# 02_-_EasyEDA.net
KiCad netlist of a schematic drawn in EasyEDA
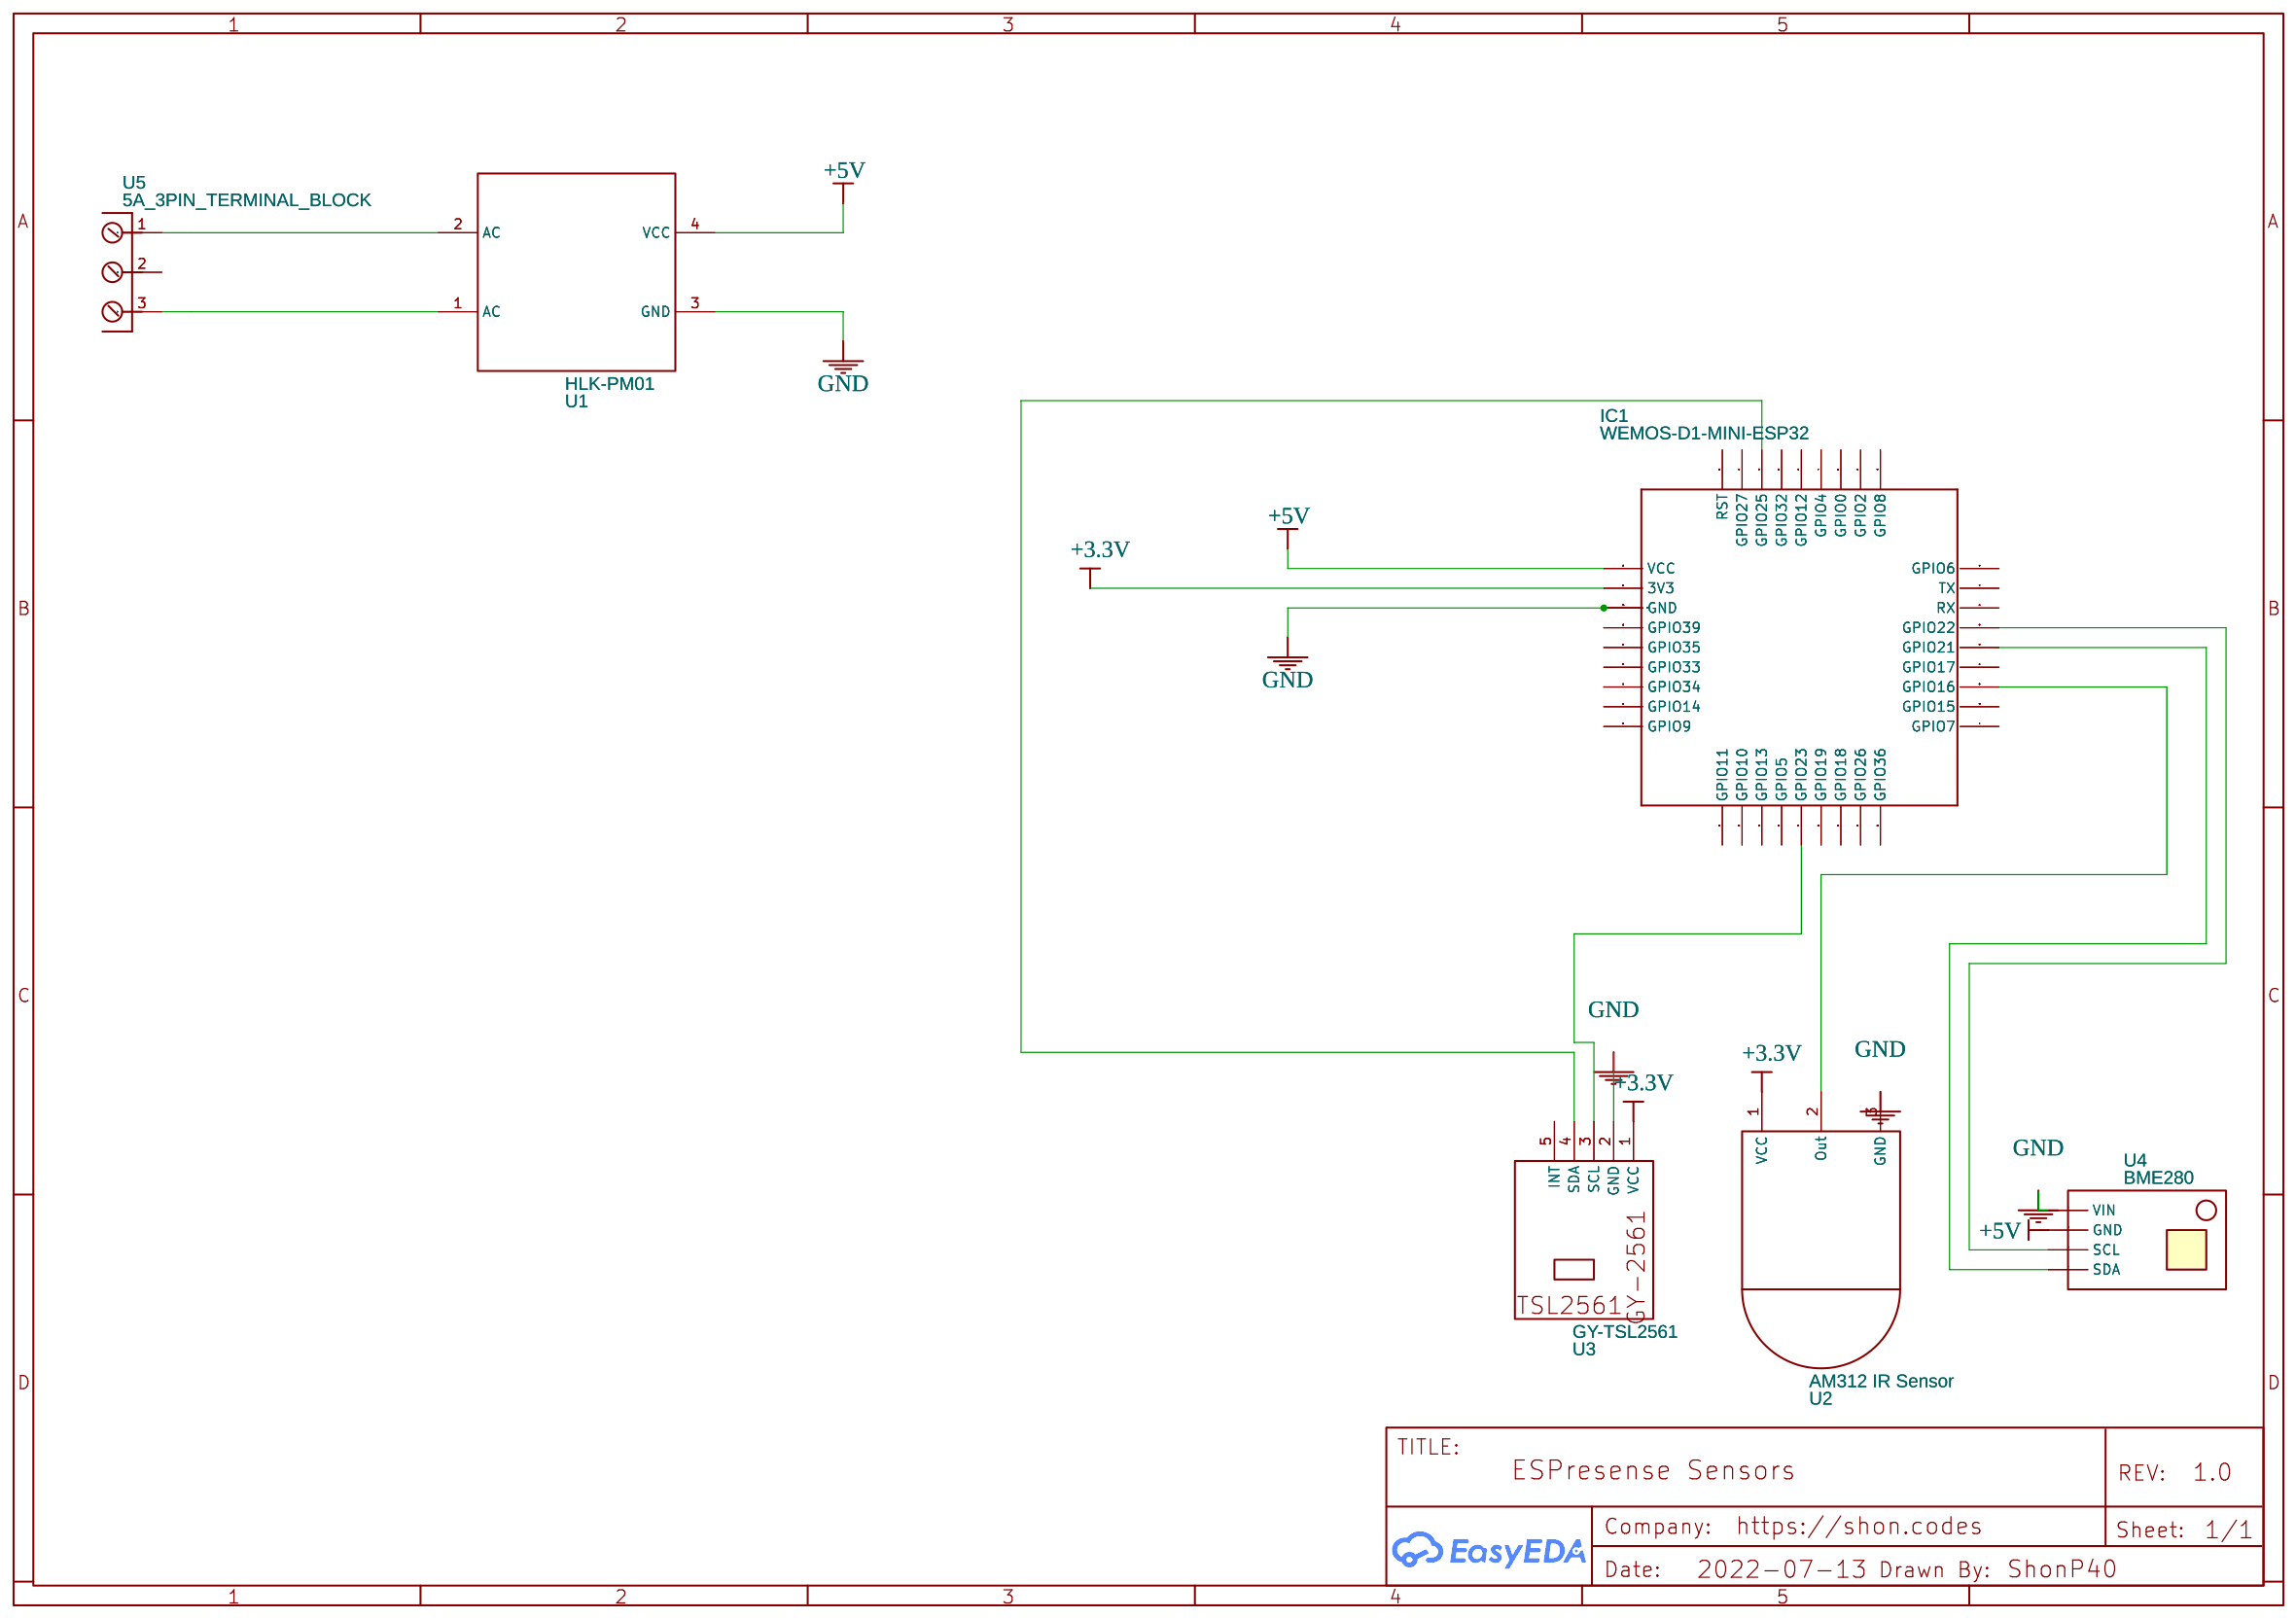
[diagram p0: schematic sheet]

(export (version "E")
  (design (tool "Eeschema 10.0.6"))
  (components
    (comp (ref "IC1") (value "WEMOS-D1-MINI-ESP32") (libsource (lib "") (part "WEMOS-D1-MINI-ESP32")))
    (comp (ref "U1") (value "HLK-PM01") (libsource (lib "") (part "HLK-PM01")))
    (comp (ref "U2") (value "AM312 IR Sensor") (libsource (lib "") (part "AM312 IR Sensor")))
    (comp (ref "U3") (value "GY-TSL2561") (libsource (lib "") (part "GY-TSL2561")))
    (comp (ref "U4") (value "BME280") (libsource (lib "") (part "BME280")))
    (comp (ref "U5") (value "5A_3PIN_TERMINAL_BLOCK") (libsource (lib "") (part "5A_3PIN_TERMINAL_BLOCK")))
  )
  (nets
    (net (code "1") (name "+3.3V") (class "Default")
      (node (ref "IC1") (pin "3V3") (pinfunction "3V3_3V3") (pintype "bidirectional"))
      (node (ref "U2") (pin "1") (pinfunction "VCC_1") (pintype "unspecified"))
      (node (ref "U3") (pin "1") (pinfunction "VCC_1") (pintype "unspecified"))
    )
    (net (code "2") (name "+5V") (class "Default")
      (node (ref "IC1") (pin "VCC") (pinfunction "VCC_VCC") (pintype "bidirectional"))
      (node (ref "U1") (pin "4") (pinfunction "VCC_4") (pintype "unspecified"))
      (node (ref "U4") (pin "2") (pinfunction "GND_2") (pintype "unspecified"))
    )
    (net (code "3") (name "GND") (class "Default")
      (node (ref "IC1") (pin "GND1") (pinfunction "GND_GND1") (pintype "bidirectional"))
      (node (ref "IC1") (pin "GND2") (pinfunction "GND_GND2") (pintype "bidirectional"))
      (node (ref "IC1") (pin "GND3") (pinfunction "GND_GND3") (pintype "bidirectional"))
      (node (ref "U1") (pin "3") (pinfunction "GND_3") (pintype "unspecified"))
      (node (ref "U2") (pin "3") (pinfunction "GND_3") (pintype "unspecified"))
      (node (ref "U3") (pin "2") (pinfunction "GND_2") (pintype "unspecified"))
      (node (ref "U4") (pin "1") (pinfunction "VIN_1") (pintype "unspecified"))
    )
    (net (code "4") (name "Net-(IC1-GPIO16)") (class "Default")
      (node (ref "IC1") (pin "16") (pinfunction "GPIO16_16") (pintype "bidirectional"))
      (node (ref "U2") (pin "2") (pinfunction "Out_2") (pintype "unspecified"))
    )
    (net (code "5") (name "Net-(IC1-GPIO21)") (class "Default")
      (node (ref "IC1") (pin "21") (pinfunction "GPIO21_21") (pintype "bidirectional"))
      (node (ref "U4") (pin "4") (pinfunction "SDA_4") (pintype "unspecified"))
    )
    (net (code "6") (name "Net-(IC1-GPIO22)") (class "Default")
      (node (ref "IC1") (pin "22") (pinfunction "GPIO22_22") (pintype "bidirectional"))
      (node (ref "U4") (pin "3") (pinfunction "SCL_3") (pintype "unspecified"))
    )
    (net (code "7") (name "Net-(IC1-GPIO23)") (class "Default")
      (node (ref "IC1") (pin "23") (pinfunction "GPIO23_23") (pintype "bidirectional"))
      (node (ref "U3") (pin "3") (pinfunction "SCL_3") (pintype "unspecified"))
    )
    (net (code "8") (name "Net-(IC1-GPIO25)") (class "Default")
      (node (ref "IC1") (pin "25") (pinfunction "GPIO25_25") (pintype "bidirectional"))
      (node (ref "U3") (pin "4") (pinfunction "SDA_4") (pintype "unspecified"))
    )
    (net (code "9") (name "Net-(U1-AC-Pad1)") (class "Default")
      (node (ref "U1") (pin "1") (pinfunction "AC_1") (pintype "unspecified"))
      (node (ref "U5") (pin "3") (pinfunction "3_3") (pintype "unspecified"))
    )
    (net (code "10") (name "Net-(U1-AC-Pad2)") (class "Default")
      (node (ref "U1") (pin "2") (pinfunction "AC_2") (pintype "unspecified"))
      (node (ref "U5") (pin "1") (pinfunction "1_1") (pintype "unspecified"))
    )
    (net (code "11") (name "unconnected-(IC1-GPIO0-Pad0)") (class "Default")
      (node (ref "IC1") (pin "0") (pinfunction "GPIO0_0") (pintype "bidirectional"))
    )
    (net (code "12") (name "unconnected-(IC1-GPIO2-Pad2)") (class "Default")
      (node (ref "IC1") (pin "2") (pinfunction "GPIO2_2") (pintype "bidirectional"))
    )
    (net (code "13") (name "unconnected-(IC1-GPIO4-Pad4)") (class "Default")
      (node (ref "IC1") (pin "4") (pinfunction "GPIO4_4") (pintype "bidirectional"))
    )
    (net (code "14") (name "unconnected-(IC1-GPIO5-Pad5)") (class "Default")
      (node (ref "IC1") (pin "5") (pinfunction "GPIO5_5") (pintype "bidirectional"))
    )
    (net (code "15") (name "unconnected-(IC1-GPIO6-Pad6)") (class "Default")
      (node (ref "IC1") (pin "6") (pinfunction "GPIO6_6") (pintype "bidirectional"))
    )
    (net (code "16") (name "unconnected-(IC1-GPIO7-Pad7)") (class "Default")
      (node (ref "IC1") (pin "7") (pinfunction "GPIO7_7") (pintype "bidirectional"))
    )
    (net (code "17") (name "unconnected-(IC1-GPIO8-Pad8)") (class "Default")
      (node (ref "IC1") (pin "8") (pinfunction "GPIO8_8") (pintype "bidirectional"))
    )
    (net (code "18") (name "unconnected-(IC1-GPIO9-Pad9)") (class "Default")
      (node (ref "IC1") (pin "9") (pinfunction "GPIO9_9") (pintype "bidirectional"))
    )
    (net (code "19") (name "unconnected-(IC1-GPIO10-Pad10)") (class "Default")
      (node (ref "IC1") (pin "10") (pinfunction "GPIO10_10") (pintype "bidirectional"))
    )
    (net (code "20") (name "unconnected-(IC1-GPIO11-Pad11)") (class "Default")
      (node (ref "IC1") (pin "11") (pinfunction "GPIO11_11") (pintype "bidirectional"))
    )
    (net (code "21") (name "unconnected-(IC1-GPIO12-Pad12)") (class "Default")
      (node (ref "IC1") (pin "12") (pinfunction "GPIO12_12") (pintype "bidirectional"))
    )
    (net (code "22") (name "unconnected-(IC1-GPIO13-Pad13)") (class "Default")
      (node (ref "IC1") (pin "13") (pinfunction "GPIO13_13") (pintype "bidirectional"))
    )
    (net (code "23") (name "unconnected-(IC1-GPIO14-Pad14)") (class "Default")
      (node (ref "IC1") (pin "14") (pinfunction "GPIO14_14") (pintype "bidirectional"))
    )
    (net (code "24") (name "unconnected-(IC1-GPIO15-Pad15)") (class "Default")
      (node (ref "IC1") (pin "15") (pinfunction "GPIO15_15") (pintype "bidirectional"))
    )
    (net (code "25") (name "unconnected-(IC1-GPIO17-Pad17)") (class "Default")
      (node (ref "IC1") (pin "17") (pinfunction "GPIO17_17") (pintype "bidirectional"))
    )
    (net (code "26") (name "unconnected-(IC1-GPIO18-Pad18)") (class "Default")
      (node (ref "IC1") (pin "18") (pinfunction "GPIO18_18") (pintype "bidirectional"))
    )
    (net (code "27") (name "unconnected-(IC1-GPIO19-Pad19)") (class "Default")
      (node (ref "IC1") (pin "19") (pinfunction "GPIO19_19") (pintype "bidirectional"))
    )
    (net (code "28") (name "unconnected-(IC1-GPIO26-Pad26)") (class "Default")
      (node (ref "IC1") (pin "26") (pinfunction "GPIO26_26") (pintype "bidirectional"))
    )
    (net (code "29") (name "unconnected-(IC1-GPIO27-Pad27)") (class "Default")
      (node (ref "IC1") (pin "27") (pinfunction "GPIO27_27") (pintype "bidirectional"))
    )
    (net (code "30") (name "unconnected-(IC1-GPIO32-Pad32)") (class "Default")
      (node (ref "IC1") (pin "32") (pinfunction "GPIO32_32") (pintype "bidirectional"))
    )
    (net (code "31") (name "unconnected-(IC1-GPIO33-Pad33)") (class "Default")
      (node (ref "IC1") (pin "33") (pinfunction "GPIO33_33") (pintype "bidirectional"))
    )
    (net (code "32") (name "unconnected-(IC1-GPIO34-Pad34)") (class "Default")
      (node (ref "IC1") (pin "34") (pinfunction "GPIO34_34") (pintype "bidirectional"))
    )
    (net (code "33") (name "unconnected-(IC1-GPIO35-Pad35)") (class "Default")
      (node (ref "IC1") (pin "35") (pinfunction "GPIO35_35") (pintype "bidirectional"))
    )
    (net (code "34") (name "unconnected-(IC1-GPIO36-Pad36)") (class "Default")
      (node (ref "IC1") (pin "36") (pinfunction "GPIO36_36") (pintype "bidirectional"))
    )
    (net (code "35") (name "unconnected-(IC1-GPIO39-Pad39)") (class "Default")
      (node (ref "IC1") (pin "39") (pinfunction "GPIO39_39") (pintype "bidirectional"))
    )
    (net (code "36") (name "unconnected-(IC1-PadRST)") (class "Default")
      (node (ref "IC1") (pin "RST") (pinfunction "RST_RST") (pintype "bidirectional"))
    )
    (net (code "37") (name "unconnected-(IC1-PadRX)") (class "Default")
      (node (ref "IC1") (pin "RX") (pinfunction "RX_RX") (pintype "bidirectional"))
    )
    (net (code "38") (name "unconnected-(IC1-PadTX)") (class "Default")
      (node (ref "IC1") (pin "TX") (pinfunction "TX_TX") (pintype "bidirectional"))
    )
    (net (code "39") (name "unconnected-(U3-INT-Pad5)") (class "Default")
      (node (ref "U3") (pin "5") (pinfunction "INT_5") (pintype "unspecified"))
    )
    (net (code "40") (name "unconnected-(U5-Pad2)") (class "Default")
      (node (ref "U5") (pin "2") (pinfunction "2_2") (pintype "unspecified"))
    )
  )
)
